# SLT3-PAY-1Q2T_P6.net
KiCad netlist of a schematic drawn in Altium Designer
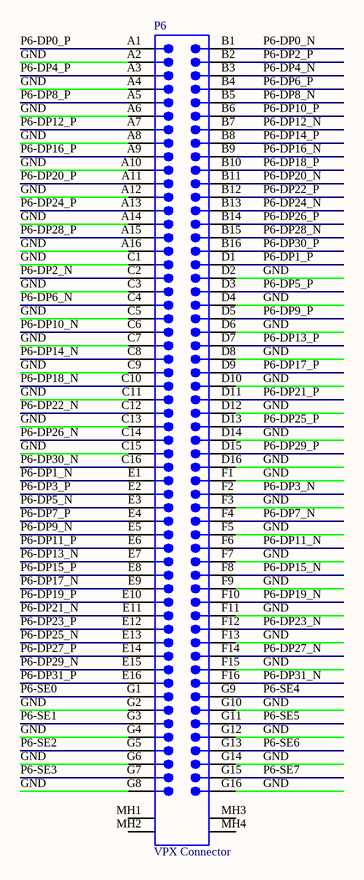
[diagram p0: SLT3-PAY-1Q2T_P6.SchDoc]

(export (version "E")
  (design (tool "Eeschema 10.0.6"))
  (components
    (comp (ref "P6")
      (value "VPX Connector")
      (footprint "BTB1-8-4H112M")
      (description "Ruggedized Board-to-Board Connector, Right Angle, 7-Row, Pitch 1.8mm, 112-Position")
      (fields (field (name "MANUFACTURER") "TE") (field (name "MANUFACTURER PART NUMBER") "2102771-1"))
      (libsource (lib "SVPX") (part "2102771-1"))
    )
  )
  (nets
    (net (code "1") (name "/GND") (class "Default")
      (node (ref "P6") (pin "A10") (pinfunction "A10_A10") (pintype "passive"))
      (node (ref "P6") (pin "A12") (pinfunction "A12_A12") (pintype "passive"))
      (node (ref "P6") (pin "A14") (pinfunction "A14_A14") (pintype "passive"))
      (node (ref "P6") (pin "A16") (pinfunction "A16_A16") (pintype "passive"))
      (node (ref "P6") (pin "A2") (pinfunction "A2_A2") (pintype "passive"))
      (node (ref "P6") (pin "A4") (pinfunction "A4_A4") (pintype "passive"))
      (node (ref "P6") (pin "A6") (pinfunction "A6_A6") (pintype "passive"))
      (node (ref "P6") (pin "A8") (pinfunction "A8_A8") (pintype "passive"))
      (node (ref "P6") (pin "C1") (pinfunction "C1_C1") (pintype "passive"))
      (node (ref "P6") (pin "C11") (pinfunction "C11_C11") (pintype "passive"))
      (node (ref "P6") (pin "C13") (pinfunction "C13_C13") (pintype "passive"))
      (node (ref "P6") (pin "C15") (pinfunction "C15_C15") (pintype "passive"))
      (node (ref "P6") (pin "C3") (pinfunction "C3_C3") (pintype "passive"))
      (node (ref "P6") (pin "C5") (pinfunction "C5_C5") (pintype "passive"))
      (node (ref "P6") (pin "C7") (pinfunction "C7_C7") (pintype "passive"))
      (node (ref "P6") (pin "C9") (pinfunction "C9_C9") (pintype "passive"))
      (node (ref "P6") (pin "D10") (pinfunction "D10_D10") (pintype "passive"))
      (node (ref "P6") (pin "D12") (pinfunction "D12_D12") (pintype "passive"))
      (node (ref "P6") (pin "D14") (pinfunction "D14_D14") (pintype "passive"))
      (node (ref "P6") (pin "D16") (pinfunction "D16_D16") (pintype "passive"))
      (node (ref "P6") (pin "D2") (pinfunction "D2_D2") (pintype "passive"))
      (node (ref "P6") (pin "D4") (pinfunction "D4_D4") (pintype "passive"))
      (node (ref "P6") (pin "D6") (pinfunction "D6_D6") (pintype "passive"))
      (node (ref "P6") (pin "D8") (pinfunction "D8_D8") (pintype "passive"))
      (node (ref "P6") (pin "F1") (pinfunction "F1_F1") (pintype "passive"))
      (node (ref "P6") (pin "F11") (pinfunction "F11_F11") (pintype "passive"))
      (node (ref "P6") (pin "F13") (pinfunction "F13_F13") (pintype "passive"))
      (node (ref "P6") (pin "F15") (pinfunction "F15_F15") (pintype "passive"))
      (node (ref "P6") (pin "F3") (pinfunction "F3_F3") (pintype "passive"))
      (node (ref "P6") (pin "F5") (pinfunction "F5_F5") (pintype "passive"))
      (node (ref "P6") (pin "F7") (pinfunction "F7_F7") (pintype "passive"))
      (node (ref "P6") (pin "F9") (pinfunction "F9_F9") (pintype "passive"))
      (node (ref "P6") (pin "G10") (pinfunction "G10_G10") (pintype "passive"))
      (node (ref "P6") (pin "G12") (pinfunction "G12_G12") (pintype "passive"))
      (node (ref "P6") (pin "G14") (pinfunction "G14_G14") (pintype "passive"))
      (node (ref "P6") (pin "G16") (pinfunction "G16_G16") (pintype "passive"))
      (node (ref "P6") (pin "G2") (pinfunction "G2_G2") (pintype "passive"))
      (node (ref "P6") (pin "G4") (pinfunction "G4_G4") (pintype "passive"))
      (node (ref "P6") (pin "G6") (pinfunction "G6_G6") (pintype "passive"))
      (node (ref "P6") (pin "G8") (pinfunction "G8_G8") (pintype "passive"))
    )
    (net (code "2") (name "/P6-DP0_N") (class "Default")
      (node (ref "P6") (pin "B1") (pinfunction "B1_B1") (pintype "passive"))
    )
    (net (code "3") (name "/P6-DP0_P") (class "Default")
      (node (ref "P6") (pin "A1") (pinfunction "A1_A1") (pintype "passive"))
    )
    (net (code "4") (name "/P6-DP1_N") (class "Default")
      (node (ref "P6") (pin "E1") (pinfunction "E1_E1") (pintype "passive"))
    )
    (net (code "5") (name "/P6-DP1_P") (class "Default")
      (node (ref "P6") (pin "D1") (pinfunction "D1_D1") (pintype "passive"))
    )
    (net (code "6") (name "/P6-DP2_N") (class "Default")
      (node (ref "P6") (pin "C2") (pinfunction "C2_C2") (pintype "passive"))
    )
    (net (code "7") (name "/P6-DP2_P") (class "Default")
      (node (ref "P6") (pin "B2") (pinfunction "B2_B2") (pintype "passive"))
    )
    (net (code "8") (name "/P6-DP3_N") (class "Default")
      (node (ref "P6") (pin "F2") (pinfunction "F2_F2") (pintype "passive"))
    )
    (net (code "9") (name "/P6-DP3_P") (class "Default")
      (node (ref "P6") (pin "E2") (pinfunction "E2_E2") (pintype "passive"))
    )
    (net (code "10") (name "/P6-DP4_N") (class "Default")
      (node (ref "P6") (pin "B3") (pinfunction "B3_B3") (pintype "passive"))
    )
    (net (code "11") (name "/P6-DP4_P") (class "Default")
      (node (ref "P6") (pin "A3") (pinfunction "A3_A3") (pintype "passive"))
    )
    (net (code "12") (name "/P6-DP5_N") (class "Default")
      (node (ref "P6") (pin "E3") (pinfunction "E3_E3") (pintype "passive"))
    )
    (net (code "13") (name "/P6-DP5_P") (class "Default")
      (node (ref "P6") (pin "D3") (pinfunction "D3_D3") (pintype "passive"))
    )
    (net (code "14") (name "/P6-DP6_N") (class "Default")
      (node (ref "P6") (pin "C4") (pinfunction "C4_C4") (pintype "passive"))
    )
    (net (code "15") (name "/P6-DP6_P") (class "Default")
      (node (ref "P6") (pin "B4") (pinfunction "B4_B4") (pintype "passive"))
    )
    (net (code "16") (name "/P6-DP7_N") (class "Default")
      (node (ref "P6") (pin "F4") (pinfunction "F4_F4") (pintype "passive"))
    )
    (net (code "17") (name "/P6-DP7_P") (class "Default")
      (node (ref "P6") (pin "E4") (pinfunction "E4_E4") (pintype "passive"))
    )
    (net (code "18") (name "/P6-DP8_N") (class "Default")
      (node (ref "P6") (pin "B5") (pinfunction "B5_B5") (pintype "passive"))
    )
    (net (code "19") (name "/P6-DP8_P") (class "Default")
      (node (ref "P6") (pin "A5") (pinfunction "A5_A5") (pintype "passive"))
    )
    (net (code "20") (name "/P6-DP9_N") (class "Default")
      (node (ref "P6") (pin "E5") (pinfunction "E5_E5") (pintype "passive"))
    )
    (net (code "21") (name "/P6-DP9_P") (class "Default")
      (node (ref "P6") (pin "D5") (pinfunction "D5_D5") (pintype "passive"))
    )
    (net (code "22") (name "/P6-DP10_N") (class "Default")
      (node (ref "P6") (pin "C6") (pinfunction "C6_C6") (pintype "passive"))
    )
    (net (code "23") (name "/P6-DP10_P") (class "Default")
      (node (ref "P6") (pin "B6") (pinfunction "B6_B6") (pintype "passive"))
    )
    (net (code "24") (name "/P6-DP11_N") (class "Default")
      (node (ref "P6") (pin "F6") (pinfunction "F6_F6") (pintype "passive"))
    )
    (net (code "25") (name "/P6-DP11_P") (class "Default")
      (node (ref "P6") (pin "E6") (pinfunction "E6_E6") (pintype "passive"))
    )
    (net (code "26") (name "/P6-DP12_N") (class "Default")
      (node (ref "P6") (pin "B7") (pinfunction "B7_B7") (pintype "passive"))
    )
    (net (code "27") (name "/P6-DP12_P") (class "Default")
      (node (ref "P6") (pin "A7") (pinfunction "A7_A7") (pintype "passive"))
    )
    (net (code "28") (name "/P6-DP13_N") (class "Default")
      (node (ref "P6") (pin "E7") (pinfunction "E7_E7") (pintype "passive"))
    )
    (net (code "29") (name "/P6-DP13_P") (class "Default")
      (node (ref "P6") (pin "D7") (pinfunction "D7_D7") (pintype "passive"))
    )
    (net (code "30") (name "/P6-DP14_N") (class "Default")
      (node (ref "P6") (pin "C8") (pinfunction "C8_C8") (pintype "passive"))
    )
    (net (code "31") (name "/P6-DP14_P") (class "Default")
      (node (ref "P6") (pin "B8") (pinfunction "B8_B8") (pintype "passive"))
    )
    (net (code "32") (name "/P6-DP15_N") (class "Default")
      (node (ref "P6") (pin "F8") (pinfunction "F8_F8") (pintype "passive"))
    )
    (net (code "33") (name "/P6-DP15_P") (class "Default")
      (node (ref "P6") (pin "E8") (pinfunction "E8_E8") (pintype "passive"))
    )
    (net (code "34") (name "/P6-DP16_N") (class "Default")
      (node (ref "P6") (pin "B9") (pinfunction "B9_B9") (pintype "passive"))
    )
    (net (code "35") (name "/P6-DP16_P") (class "Default")
      (node (ref "P6") (pin "A9") (pinfunction "A9_A9") (pintype "passive"))
    )
    (net (code "36") (name "/P6-DP17_N") (class "Default")
      (node (ref "P6") (pin "E9") (pinfunction "E9_E9") (pintype "passive"))
    )
    (net (code "37") (name "/P6-DP17_P") (class "Default")
      (node (ref "P6") (pin "D9") (pinfunction "D9_D9") (pintype "passive"))
    )
    (net (code "38") (name "/P6-DP18_N") (class "Default")
      (node (ref "P6") (pin "C10") (pinfunction "C10_C10") (pintype "passive"))
    )
    (net (code "39") (name "/P6-DP18_P") (class "Default")
      (node (ref "P6") (pin "B10") (pinfunction "B10_B10") (pintype "passive"))
    )
    (net (code "40") (name "/P6-DP19_N") (class "Default")
      (node (ref "P6") (pin "F10") (pinfunction "F10_F10") (pintype "passive"))
    )
    (net (code "41") (name "/P6-DP19_P") (class "Default")
      (node (ref "P6") (pin "E10") (pinfunction "E10_E10") (pintype "passive"))
    )
    (net (code "42") (name "/P6-DP20_N") (class "Default")
      (node (ref "P6") (pin "B11") (pinfunction "B11_B11") (pintype "passive"))
    )
    (net (code "43") (name "/P6-DP20_P") (class "Default")
      (node (ref "P6") (pin "A11") (pinfunction "A11_A11") (pintype "passive"))
    )
    (net (code "44") (name "/P6-DP21_N") (class "Default")
      (node (ref "P6") (pin "E11") (pinfunction "E11_E11") (pintype "passive"))
    )
    (net (code "45") (name "/P6-DP21_P") (class "Default")
      (node (ref "P6") (pin "D11") (pinfunction "D11_D11") (pintype "passive"))
    )
    (net (code "46") (name "/P6-DP22_N") (class "Default")
      (node (ref "P6") (pin "C12") (pinfunction "C12_C12") (pintype "passive"))
    )
    (net (code "47") (name "/P6-DP22_P") (class "Default")
      (node (ref "P6") (pin "B12") (pinfunction "B12_B12") (pintype "passive"))
    )
    (net (code "48") (name "/P6-DP23_N") (class "Default")
      (node (ref "P6") (pin "F12") (pinfunction "F12_F12") (pintype "passive"))
    )
    (net (code "49") (name "/P6-DP23_P") (class "Default")
      (node (ref "P6") (pin "E12") (pinfunction "E12_E12") (pintype "passive"))
    )
    (net (code "50") (name "/P6-DP24_N") (class "Default")
      (node (ref "P6") (pin "B13") (pinfunction "B13_B13") (pintype "passive"))
    )
    (net (code "51") (name "/P6-DP24_P") (class "Default")
      (node (ref "P6") (pin "A13") (pinfunction "A13_A13") (pintype "passive"))
    )
    (net (code "52") (name "/P6-DP25_N") (class "Default")
      (node (ref "P6") (pin "E13") (pinfunction "E13_E13") (pintype "passive"))
    )
    (net (code "53") (name "/P6-DP25_P") (class "Default")
      (node (ref "P6") (pin "D13") (pinfunction "D13_D13") (pintype "passive"))
    )
    (net (code "54") (name "/P6-DP26_N") (class "Default")
      (node (ref "P6") (pin "C14") (pinfunction "C14_C14") (pintype "passive"))
    )
    (net (code "55") (name "/P6-DP26_P") (class "Default")
      (node (ref "P6") (pin "B14") (pinfunction "B14_B14") (pintype "passive"))
    )
    (net (code "56") (name "/P6-DP27_N") (class "Default")
      (node (ref "P6") (pin "F14") (pinfunction "F14_F14") (pintype "passive"))
    )
    (net (code "57") (name "/P6-DP27_P") (class "Default")
      (node (ref "P6") (pin "E14") (pinfunction "E14_E14") (pintype "passive"))
    )
    (net (code "58") (name "/P6-DP28_N") (class "Default")
      (node (ref "P6") (pin "B15") (pinfunction "B15_B15") (pintype "passive"))
    )
    (net (code "59") (name "/P6-DP28_P") (class "Default")
      (node (ref "P6") (pin "A15") (pinfunction "A15_A15") (pintype "passive"))
    )
    (net (code "60") (name "/P6-DP29_N") (class "Default")
      (node (ref "P6") (pin "E15") (pinfunction "E15_E15") (pintype "passive"))
    )
    (net (code "61") (name "/P6-DP29_P") (class "Default")
      (node (ref "P6") (pin "D15") (pinfunction "D15_D15") (pintype "passive"))
    )
    (net (code "62") (name "/P6-DP30_N") (class "Default")
      (node (ref "P6") (pin "C16") (pinfunction "C16_C16") (pintype "passive"))
    )
    (net (code "63") (name "/P6-DP30_P") (class "Default")
      (node (ref "P6") (pin "B16") (pinfunction "B16_B16") (pintype "passive"))
    )
    (net (code "64") (name "/P6-DP31_N") (class "Default")
      (node (ref "P6") (pin "F16") (pinfunction "F16_F16") (pintype "passive"))
    )
    (net (code "65") (name "/P6-DP31_P") (class "Default")
      (node (ref "P6") (pin "E16") (pinfunction "E16_E16") (pintype "passive"))
    )
    (net (code "66") (name "/P6-SE0") (class "Default")
      (node (ref "P6") (pin "G1") (pinfunction "G1_G1") (pintype "passive"))
    )
    (net (code "67") (name "/P6-SE1") (class "Default")
      (node (ref "P6") (pin "G3") (pinfunction "G3_G3") (pintype "passive"))
    )
    (net (code "68") (name "/P6-SE2") (class "Default")
      (node (ref "P6") (pin "G5") (pinfunction "G5_G5") (pintype "passive"))
    )
    (net (code "69") (name "/P6-SE3") (class "Default")
      (node (ref "P6") (pin "G7") (pinfunction "G7_G7") (pintype "passive"))
    )
    (net (code "70") (name "/P6-SE4") (class "Default")
      (node (ref "P6") (pin "G9") (pinfunction "G9_G9") (pintype "passive"))
    )
    (net (code "71") (name "/P6-SE5") (class "Default")
      (node (ref "P6") (pin "G11") (pinfunction "G11_G11") (pintype "passive"))
    )
    (net (code "72") (name "/P6-SE6") (class "Default")
      (node (ref "P6") (pin "G13") (pinfunction "G13_G13") (pintype "passive"))
    )
    (net (code "73") (name "/P6-SE7") (class "Default")
      (node (ref "P6") (pin "G15") (pinfunction "G15_G15") (pintype "passive"))
    )
    (net (code "74") (name "unconnected-(P6-PadMH1)") (class "Default")
      (node (ref "P6") (pin "MH1") (pinfunction "MH1_MH1") (pintype "passive"))
    )
    (net (code "75") (name "unconnected-(P6-PadMH2)") (class "Default")
      (node (ref "P6") (pin "MH2") (pinfunction "MH2_MH2") (pintype "passive"))
    )
    (net (code "76") (name "unconnected-(P6-PadMH3)") (class "Default")
      (node (ref "P6") (pin "MH3") (pinfunction "MH3_MH3") (pintype "passive"))
    )
    (net (code "77") (name "unconnected-(P6-PadMH4)") (class "Default")
      (node (ref "P6") (pin "MH4") (pinfunction "MH4_MH4") (pintype "passive"))
    )
  )
)
